# oec.net
KiCad netlist of a schematic drawn in EAGLE
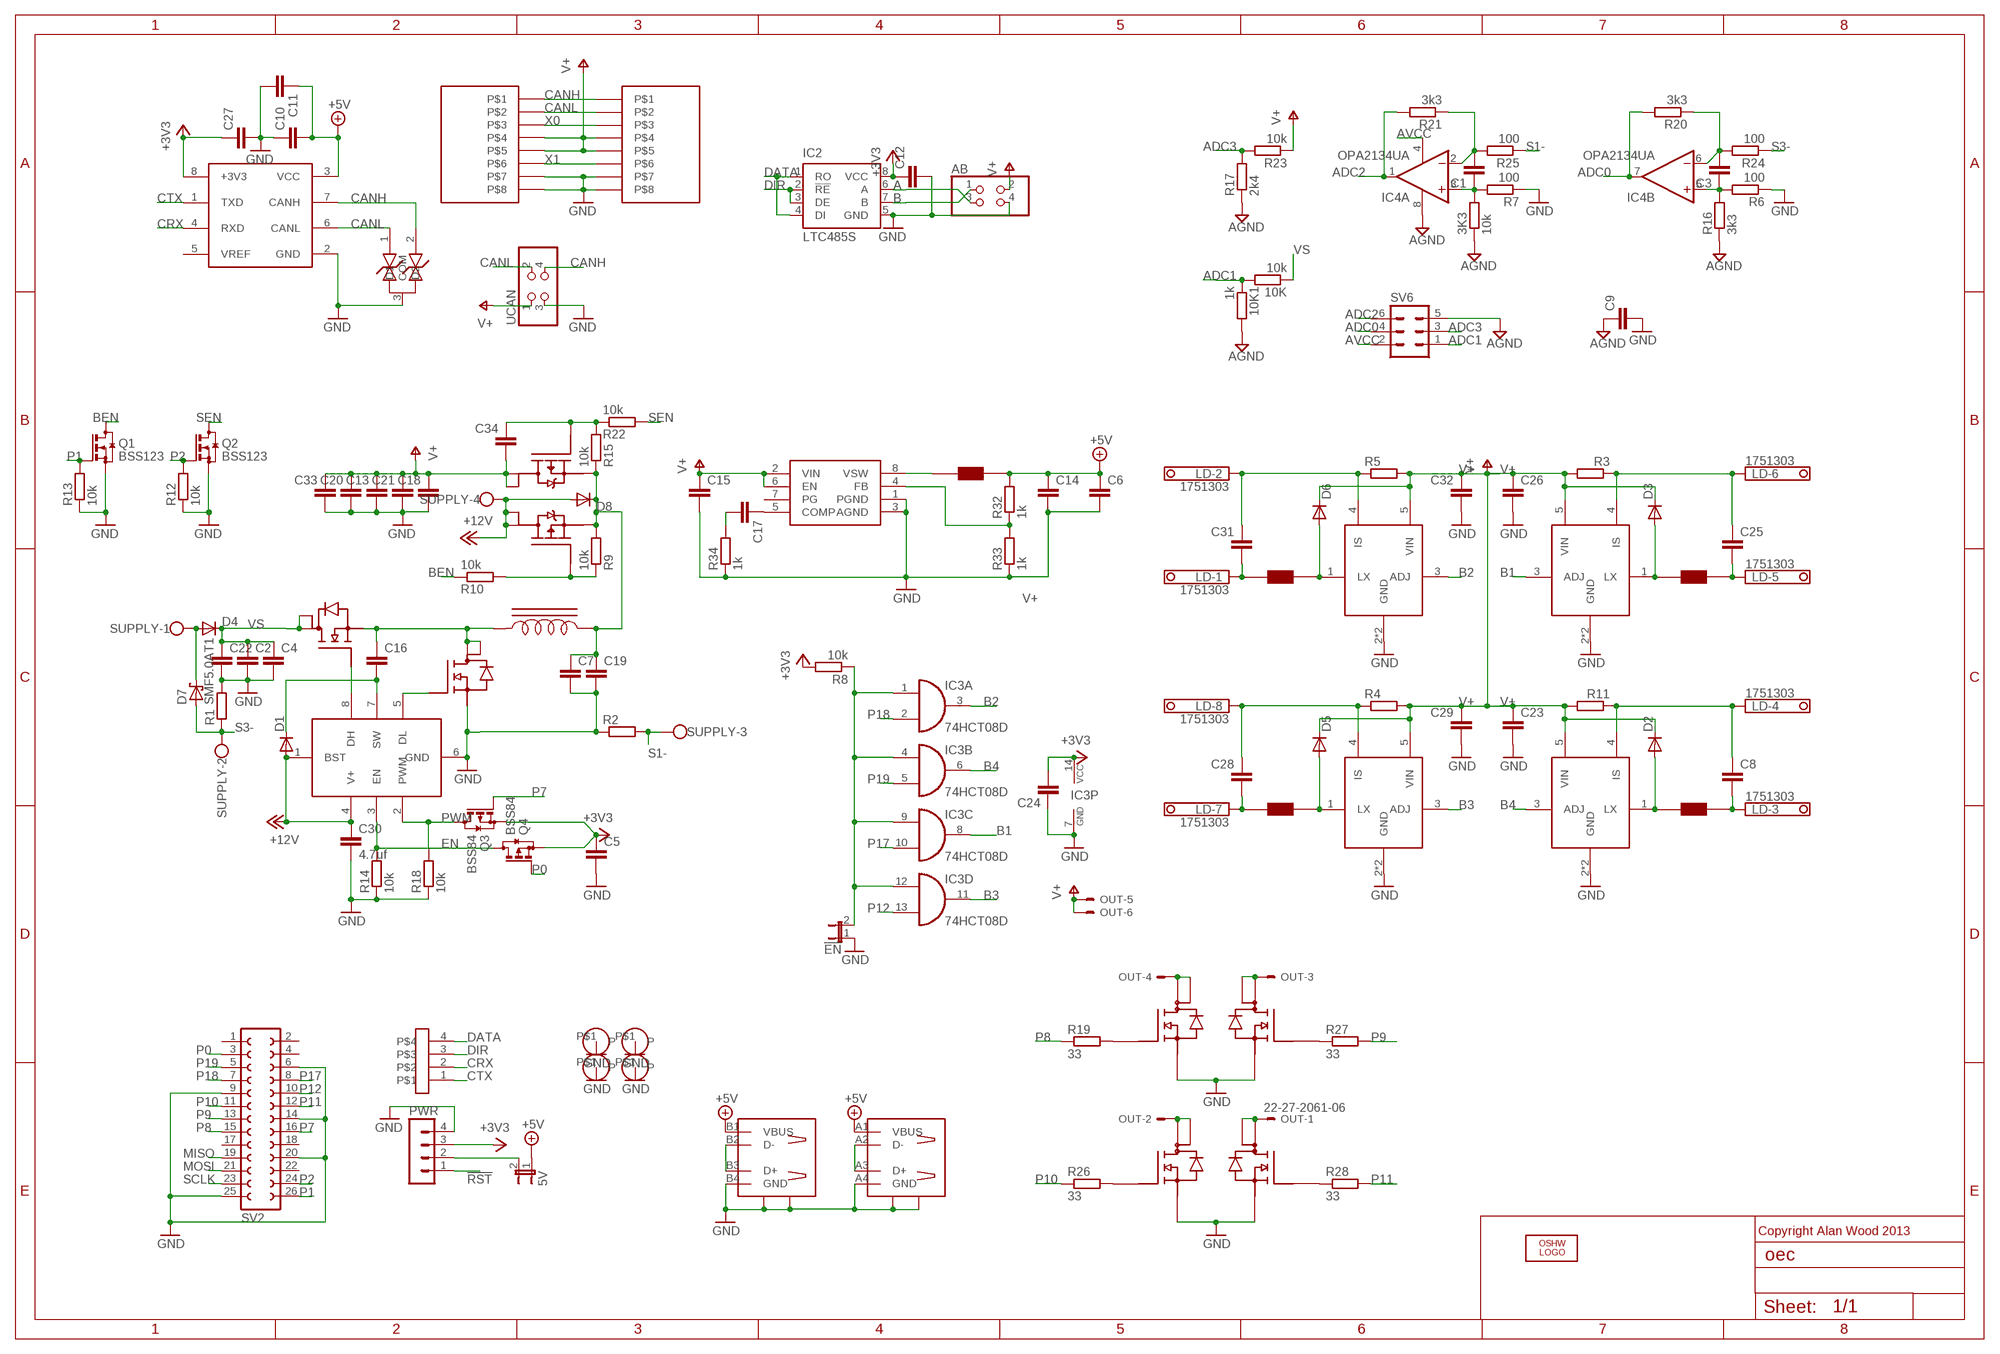
[diagram p0: schematic, sheet 1]

(export (version "E")
  (design (tool "Eeschema 10.0.6"))
  (components
    (comp (ref "!EN")
      (value "JP1E")
      (footprint "eagle-import:JP1")
      (libsource (lib "eagle-import") (part "JP1E"))
    )
    (comp (ref "3K3")
      (value "10k")
      (footprint "eagle-import:R0805")
      (libsource (lib "eagle-import") (part "R-EU_R0805"))
    )
    (comp (ref "5V")
      (value "JP1E")
      (footprint "eagle-import:JP1")
      (libsource (lib "eagle-import") (part "JP1E"))
    )
    (comp (ref "10K")
      (value "10k")
      (footprint "eagle-import:R0805")
      (libsource (lib "eagle-import") (part "R-EU_R0805"))
    )
    (comp (ref "10K1")
      (value "1k")
      (footprint "eagle-import:R0805")
      (libsource (lib "eagle-import") (part "R-EU_R0805"))
    )
    (comp (ref "AB")
      (value "PINHD-2X2/90")
      (footprint "eagle-import:2X02_90")
      (libsource (lib "eagle-import") (part "PINHD-2X2/90"))
    )
    (comp (ref "C1")
      (value "C-EUC0805")
      (footprint "eagle-import:C0805")
      (libsource (lib "eagle-import") (part "C-EUC0805"))
    )
    (comp (ref "C2")
      (value "C-EUC1210")
      (footprint "eagle-import:C1210")
      (libsource (lib "eagle-import") (part "C-EUC1210"))
    )
    (comp (ref "C3")
      (value "C-EUC0805")
      (footprint "eagle-import:C0805")
      (libsource (lib "eagle-import") (part "C-EUC0805"))
    )
    (comp (ref "C4")
      (value "C-EUC1210")
      (footprint "eagle-import:C1210")
      (libsource (lib "eagle-import") (part "C-EUC1210"))
    )
    (comp (ref "C5")
      (value "C-EUC0805")
      (footprint "eagle-import:C0805")
      (libsource (lib "eagle-import") (part "C-EUC0805"))
    )
    (comp (ref "C6")
      (value "C-EUC1210")
      (footprint "eagle-import:C1210")
      (libsource (lib "eagle-import") (part "C-EUC1210"))
    )
    (comp (ref "C7")
      (value "C-EUC1210")
      (footprint "eagle-import:C1210")
      (libsource (lib "eagle-import") (part "C-EUC1210"))
    )
    (comp (ref "C8")
      (value "C-EUC1210")
      (footprint "eagle-import:C1210")
      (libsource (lib "eagle-import") (part "C-EUC1210"))
    )
    (comp (ref "C9")
      (value "C-EUC0805")
      (footprint "eagle-import:C0805")
      (libsource (lib "eagle-import") (part "C-EUC0805"))
    )
    (comp (ref "C10")
      (value "C-EUC1210")
      (footprint "eagle-import:C1210")
      (libsource (lib "eagle-import") (part "C-EUC1210"))
    )
    (comp (ref "C11")
      (value "C-EUC1210")
      (footprint "eagle-import:C1210")
      (libsource (lib "eagle-import") (part "C-EUC1210"))
    )
    (comp (ref "C12")
      (value "C-EUC0805")
      (footprint "eagle-import:C0805")
      (libsource (lib "eagle-import") (part "C-EUC0805"))
    )
    (comp (ref "C13")
      (value "C-EUC1210")
      (footprint "eagle-import:C1210")
      (libsource (lib "eagle-import") (part "C-EUC1210"))
    )
    (comp (ref "C14")
      (value "C-EUC1210")
      (footprint "eagle-import:C1210")
      (libsource (lib "eagle-import") (part "C-EUC1210"))
    )
    (comp (ref "C15")
      (value "C-EUC0805")
      (footprint "eagle-import:C0805")
      (libsource (lib "eagle-import") (part "C-EUC0805"))
    )
    (comp (ref "C16")
      (value "C-EUC0805")
      (footprint "eagle-import:C0805")
      (libsource (lib "eagle-import") (part "C-EUC0805"))
    )
    (comp (ref "C17")
      (value "C-EUC0805")
      (footprint "eagle-import:C0805")
      (libsource (lib "eagle-import") (part "C-EUC0805"))
    )
    (comp (ref "C18")
      (value "C-EUC1210")
      (footprint "eagle-import:C1210")
      (libsource (lib "eagle-import") (part "C-EUC1210"))
    )
    (comp (ref "C19")
      (value "C-EUC1210")
      (footprint "eagle-import:C1210")
      (libsource (lib "eagle-import") (part "C-EUC1210"))
    )
    (comp (ref "C20")
      (value "C-EUC1210")
      (footprint "eagle-import:C1210")
      (libsource (lib "eagle-import") (part "C-EUC1210"))
    )
    (comp (ref "C21")
      (value "C-EUC1210")
      (footprint "eagle-import:C1210")
      (libsource (lib "eagle-import") (part "C-EUC1210"))
    )
    (comp (ref "C22")
      (value "C-EUC1210")
      (footprint "eagle-import:C1210")
      (libsource (lib "eagle-import") (part "C-EUC1210"))
    )
    (comp (ref "C23")
      (value "C-EUC1210")
      (footprint "eagle-import:C1210")
      (libsource (lib "eagle-import") (part "C-EUC1210"))
    )
    (comp (ref "C24")
      (value "C-EUC0805")
      (footprint "eagle-import:C0805")
      (libsource (lib "eagle-import") (part "C-EUC0805"))
    )
    (comp (ref "C25")
      (value "C-EUC1210")
      (footprint "eagle-import:C1210")
      (libsource (lib "eagle-import") (part "C-EUC1210"))
    )
    (comp (ref "C26")
      (value "C-EUC1210")
      (footprint "eagle-import:C1210")
      (libsource (lib "eagle-import") (part "C-EUC1210"))
    )
    (comp (ref "C27")
      (value "C-EUC0805")
      (footprint "eagle-import:C0805")
      (libsource (lib "eagle-import") (part "C-EUC0805"))
    )
    (comp (ref "C28")
      (value "C-EUC1210")
      (footprint "eagle-import:C1210")
      (libsource (lib "eagle-import") (part "C-EUC1210"))
    )
    (comp (ref "C29")
      (value "C-EUC1210")
      (footprint "eagle-import:C1210")
      (libsource (lib "eagle-import") (part "C-EUC1210"))
    )
    (comp (ref "C30")
      (value "4.7uf")
      (footprint "eagle-import:C0805")
      (libsource (lib "eagle-import") (part "C-EUC0805"))
    )
    (comp (ref "C31")
      (value "C-EUC1210")
      (footprint "eagle-import:C1210")
      (libsource (lib "eagle-import") (part "C-EUC1210"))
    )
    (comp (ref "C32")
      (value "C-EUC1210")
      (footprint "eagle-import:C1210")
      (libsource (lib "eagle-import") (part "C-EUC1210"))
    )
    (comp (ref "C33")
      (value "C-EUC1210")
      (footprint "eagle-import:C1210")
      (libsource (lib "eagle-import") (part "C-EUC1210"))
    )
    (comp (ref "C34")
      (value "C-EUC0805")
      (footprint "eagle-import:C0805")
      (libsource (lib "eagle-import") (part "C-EUC0805"))
    )
    (comp (ref "COM")
      (value "4X1X2.54-HEADER")
      (footprint "eagle-import:2.54_HEADER_4W")
      (libsource (lib "eagle-import") (part "4X1X2.54-HEADER"))
    )
    (comp (ref "D1")
      (value "DIODE-SOD123")
      (footprint "eagle-import:SOD123")
      (libsource (lib "eagle-import") (part "DIODE-SOD123"))
    )
    (comp (ref "D2")
      (value "DIODE-SOD123")
      (footprint "eagle-import:SOD123")
      (libsource (lib "eagle-import") (part "DIODE-SOD123"))
    )
    (comp (ref "D3")
      (value "DIODE-SOD123")
      (footprint "eagle-import:SOD123")
      (libsource (lib "eagle-import") (part "DIODE-SOD123"))
    )
    (comp (ref "D4")
      (value "DIODE-DO214AC")
      (footprint "eagle-import:DO214AC")
      (libsource (lib "eagle-import") (part "DIODE-DO214AC"))
    )
    (comp (ref "D5")
      (value "DIODE-SOD123")
      (footprint "eagle-import:SOD123")
      (libsource (lib "eagle-import") (part "DIODE-SOD123"))
    )
    (comp (ref "D6")
      (value "DIODE-SOD123")
      (footprint "eagle-import:SOD123")
      (libsource (lib "eagle-import") (part "DIODE-SOD123"))
    )
    (comp (ref "D7")
      (value "SMF5.0AT1")
      (footprint "eagle-import:SOD123FL")
      (libsource (lib "eagle-import") (part "SMF5.0AT1"))
    )
    (comp (ref "D8")
      (value "DIODE-DO214AC")
      (footprint "eagle-import:DO214AC")
      (libsource (lib "eagle-import") (part "DIODE-DO214AC"))
    )
    (comp (ref "IC2")
      (value "LTC485S")
      (footprint "eagle-import:SOIC8")
      (libsource (lib "eagle-import") (part "LTC485S"))
    )
    (comp (ref "IC3")
      (value "74HCT08D")
      (footprint "eagle-import:SO14")
      (libsource (lib "eagle-import") (part "7408DHCT"))
    )
    (comp (ref "IC4")
      (value "OPA2134UA")
      (footprint "eagle-import:SO08")
      (libsource (lib "eagle-import") (part "OPA2UA134"))
    )
    (comp (ref "LD")
      (value "1751303")
      (footprint "eagle-import:1751303")
      (libsource (lib "eagle-import") (part "1751303"))
    )
    (comp (ref "LOGO1")
      (value "OSHW_LOGO_FILLX0200-NT")
      (footprint "eagle-import:OSHW_FILLX200_NOTEXT")
      (libsource (lib "eagle-import") (part "OSHW_LOGO_FILLX0200-NT"))
    )
    (comp (ref "OUT")
      (value "22-27-2061-06")
      (footprint "eagle-import:6410-06")
      (libsource (lib "eagle-import") (part "22-?-0627-2061"))
    )
    (comp (ref "PWR")
      (value "MA04-1")
      (footprint "eagle-import:MA04-1")
      (libsource (lib "eagle-import") (part "MA04-1"))
    )
    (comp (ref "Q1")
      (value "BSS123")
      (footprint "eagle-import:SOT23")
      (libsource (lib "eagle-import") (part "BSS123"))
    )
    (comp (ref "Q2")
      (value "BSS123")
      (footprint "eagle-import:SOT23")
      (libsource (lib "eagle-import") (part "BSS123"))
    )
    (comp (ref "Q3")
      (value "BSS84")
      (footprint "eagle-import:SOT23")
      (libsource (lib "eagle-import") (part "BSS84"))
    )
    (comp (ref "Q4")
      (value "BSS84")
      (footprint "eagle-import:SOT23")
      (libsource (lib "eagle-import") (part "BSS84"))
    )
    (comp (ref "R1")
      (value "R-EU_R1206")
      (footprint "eagle-import:R1206")
      (libsource (lib "eagle-import") (part "resistor_R-EU_R1206"))
    )
    (comp (ref "R2")
      (value "R-EU_R1206")
      (footprint "eagle-import:R1206")
      (libsource (lib "eagle-import") (part "resistor_R-EU_R1206"))
    )
    (comp (ref "R3")
      (value "R-EU_R1210")
      (footprint "eagle-import:R1210")
      (libsource (lib "eagle-import") (part "resistor_R-EU_R1210"))
    )
    (comp (ref "R4")
      (value "R-EU_R1210")
      (footprint "eagle-import:R1210")
      (libsource (lib "eagle-import") (part "resistor_R-EU_R1210"))
    )
    (comp (ref "R5")
      (value "R-EU_R1210")
      (footprint "eagle-import:R1210")
      (libsource (lib "eagle-import") (part "resistor_R-EU_R1210"))
    )
    (comp (ref "R6")
      (value "100")
      (footprint "eagle-import:R0805")
      (libsource (lib "eagle-import") (part "R-EU_R0805"))
    )
    (comp (ref "R7")
      (value "100")
      (footprint "eagle-import:R0805")
      (libsource (lib "eagle-import") (part "R-EU_R0805"))
    )
    (comp (ref "R8")
      (value "10k")
      (footprint "eagle-import:R0805")
      (libsource (lib "eagle-import") (part "R-EU_R0805"))
    )
    (comp (ref "R9")
      (value "10k")
      (footprint "eagle-import:R0805")
      (libsource (lib "eagle-import") (part "R-EU_R0805"))
    )
    (comp (ref "R10")
      (value "10k")
      (footprint "eagle-import:R0805")
      (libsource (lib "eagle-import") (part "R-EU_R0805"))
    )
    (comp (ref "R11")
      (value "R-EU_R1210")
      (footprint "eagle-import:R1210")
      (libsource (lib "eagle-import") (part "resistor_R-EU_R1210"))
    )
    (comp (ref "R12")
      (value "10k")
      (footprint "eagle-import:R0805")
      (libsource (lib "eagle-import") (part "R-EU_R0805"))
    )
    (comp (ref "R13")
      (value "10k")
      (footprint "eagle-import:R0805")
      (libsource (lib "eagle-import") (part "R-EU_R0805"))
    )
    (comp (ref "R14")
      (value "10k")
      (footprint "eagle-import:R0805")
      (libsource (lib "eagle-import") (part "R-EU_R0805"))
    )
    (comp (ref "R15")
      (value "10k")
      (footprint "eagle-import:R0805")
      (libsource (lib "eagle-import") (part "R-EU_R0805"))
    )
    (comp (ref "R16")
      (value "3k3")
      (footprint "eagle-import:R0805")
      (libsource (lib "eagle-import") (part "R-EU_R0805"))
    )
    (comp (ref "R17")
      (value "2k4")
      (footprint "eagle-import:R0805")
      (libsource (lib "eagle-import") (part "R-EU_R0805"))
    )
    (comp (ref "R18")
      (value "10k")
      (footprint "eagle-import:R0805")
      (libsource (lib "eagle-import") (part "R-EU_R0805"))
    )
    (comp (ref "R19")
      (value "33")
      (footprint "eagle-import:R0603")
      (libsource (lib "eagle-import") (part "resistor_R-EU_R0603"))
    )
    (comp (ref "R20")
      (value "3k3")
      (footprint "eagle-import:R0805")
      (libsource (lib "eagle-import") (part "R-EU_R0805"))
    )
    (comp (ref "R21")
      (value "3k3")
      (footprint "eagle-import:R0805")
      (libsource (lib "eagle-import") (part "R-EU_R0805"))
    )
    (comp (ref "R22")
      (value "10k")
      (footprint "eagle-import:R0805")
      (libsource (lib "eagle-import") (part "R-EU_R0805"))
    )
    (comp (ref "R23")
      (value "10k")
      (footprint "eagle-import:R0805")
      (libsource (lib "eagle-import") (part "R-EU_R0805"))
    )
    (comp (ref "R24")
      (value "100")
      (footprint "eagle-import:R0805")
      (libsource (lib "eagle-import") (part "R-EU_R0805"))
    )
    (comp (ref "R25")
      (value "100")
      (footprint "eagle-import:R0805")
      (libsource (lib "eagle-import") (part "R-EU_R0805"))
    )
    (comp (ref "R26")
      (value "33")
      (footprint "eagle-import:R0603")
      (libsource (lib "eagle-import") (part "resistor_R-EU_R0603"))
    )
    (comp (ref "R27")
      (value "33")
      (footprint "eagle-import:R0603")
      (libsource (lib "eagle-import") (part "resistor_R-EU_R0603"))
    )
    (comp (ref "R28")
      (value "33")
      (footprint "eagle-import:R0603")
      (libsource (lib "eagle-import") (part "resistor_R-EU_R0603"))
    )
    (comp (ref "R32")
      (value "1k")
      (footprint "eagle-import:R0805")
      (libsource (lib "eagle-import") (part "R-EU_R0805"))
    )
    (comp (ref "R33")
      (value "1k")
      (footprint "eagle-import:R0805")
      (libsource (lib "eagle-import") (part "R-EU_R0805"))
    )
    (comp (ref "R34")
      (value "1k")
      (footprint "eagle-import:R0805")
      (libsource (lib "eagle-import") (part "R-EU_R0805"))
    )
    (comp (ref "SUPPLY")
      (value "W237-4")
      (footprint "eagle-import:W237-4")
      (libsource (lib "eagle-import") (part "W237-4"))
    )
    (comp (ref "SV2")
      (value "FE13-2")
      (footprint "eagle-import:FE13-2")
      (libsource (lib "eagle-import") (part "FE13-2"))
    )
    (comp (ref "SV6")
      (value "MA03-2")
      (footprint "eagle-import:MA03-2")
      (libsource (lib "eagle-import") (part "MA03-2"))
    )
    (comp (ref "U$1")
      (value "HOLE-2.5MM")
      (footprint "eagle-import:2.5MM-HOLE")
      (libsource (lib "eagle-import") (part "HOLE-2.5MM"))
    )
    (comp (ref "U$2")
      (value "HOLE-2.5MM")
      (footprint "eagle-import:2.5MM-HOLE")
      (libsource (lib "eagle-import") (part "HOLE-2.5MM"))
    )
    (comp (ref "U$3")
      (value "HOLE-2.5MM")
      (footprint "eagle-import:2.5MM-HOLE")
      (libsource (lib "eagle-import") (part "HOLE-2.5MM"))
    )
    (comp (ref "U$4")
      (value "HOLE-2.5MM")
      (footprint "eagle-import:2.5MM-HOLE")
      (libsource (lib "eagle-import") (part "HOLE-2.5MM"))
    )
    (comp (ref "U$5")
      (value "NCP3170SOIC-8")
      (footprint "eagle-import:SOIC-8-NARROW")
      (libsource (lib "eagle-import") (part "NCP3170SOIC-8"))
    )
    (comp (ref "U$6")
      (value "NTMD4820NR2G")
      (footprint "eagle-import:SOIC-8-NARROW")
      (libsource (lib "eagle-import") (part "NTMD4820NR2G"))
    )
    (comp (ref "U$7")
      (value "AMIS-3063")
      (footprint "eagle-import:SOIC-8-NARROW")
      (libsource (lib "eagle-import") (part "AMIS-3063"))
    )
    (comp (ref "U$8")
      (value "NTMD4820NR2G")
      (footprint "eagle-import:SOIC-8-NARROW")
      (libsource (lib "eagle-import") (part "NTMD4820NR2G"))
    )
    (comp (ref "U$9")
      (value "NRS6045T330MMGK")
      (footprint "eagle-import:TAIKO-YUDEN-6045")
      (libsource (lib "eagle-import") (part "NRS6045T330MMGK"))
    )
    (comp (ref "U$12")
      (value "NCP3420")
      (footprint "eagle-import:SO8")
      (libsource (lib "eagle-import") (part "NCP3420"))
    )
    (comp (ref "U$13")
      (value "RJHSE-5080")
      (footprint "eagle-import:RJ45")
      (libsource (lib "eagle-import") (part "RJHSE-5080"))
    )
    (comp (ref "U$14")
      (value "RJHSE-5080")
      (footprint "eagle-import:RJ45")
      (libsource (lib "eagle-import") (part "RJHSE-5080"))
    )
    (comp (ref "U$15")
      (value "DR127-XXX")
      (footprint "eagle-import:DR127")
      (libsource (lib "eagle-import") (part "DR127-XXX"))
    )
    (comp (ref "U$16")
      (value "DUAL-USBA-PTH-5787617-1")
      (footprint "eagle-import:DUAL-USBA-PTH")
      (libsource (lib "eagle-import") (part "DUAL-USBA-PTH-5787617-1"))
    )
    (comp (ref "U$17")
      (value "NUP2105L")
      (footprint "eagle-import:SOT23")
      (libsource (lib "eagle-import") (part "NUP2105L"))
    )
    (comp (ref "U$19")
      (value "SI49255DD")
      (footprint "eagle-import:SO8")
      (libsource (lib "eagle-import") (part "SI49255DD"))
    )
    (comp (ref "U$20")
      (value "IRF9358PBF")
      (footprint "eagle-import:SO8")
      (libsource (lib "eagle-import") (part "IRF9358PBF"))
    )
    (comp (ref "U$25")
      (value "ZLED7X20")
      (footprint "eagle-import:SOT89-5")
      (libsource (lib "eagle-import") (part "ZLED7X20"))
    )
    (comp (ref "U$27")
      (value "ZLED7X20")
      (footprint "eagle-import:SOT89-5")
      (libsource (lib "eagle-import") (part "ZLED7X20"))
    )
    (comp (ref "U$29")
      (value "ZLED7X20")
      (footprint "eagle-import:SOT89-5")
      (libsource (lib "eagle-import") (part "ZLED7X20"))
    )
    (comp (ref "U$31")
      (value "ZLED7X20")
      (footprint "eagle-import:SOT89-5")
      (libsource (lib "eagle-import") (part "ZLED7X20"))
    )
    (comp (ref "U$33")
      (value "NR5040T330M")
      (footprint "eagle-import:TAIKO-YUDEN-5040")
      (libsource (lib "eagle-import") (part "NR5040T330M"))
    )
    (comp (ref "U$34")
      (value "NR5040T330M")
      (footprint "eagle-import:TAIKO-YUDEN-5040")
      (libsource (lib "eagle-import") (part "NR5040T330M"))
    )
    (comp (ref "U$35")
      (value "NR5040T330M")
      (footprint "eagle-import:TAIKO-YUDEN-5040")
      (libsource (lib "eagle-import") (part "NR5040T330M"))
    )
    (comp (ref "U$36")
      (value "NR5040T330M")
      (footprint "eagle-import:TAIKO-YUDEN-5040")
      (libsource (lib "eagle-import") (part "NR5040T330M"))
    )
    (comp (ref "UCAN")
      (value "PINHD-2X2")
      (footprint "eagle-import:2X02")
      (libsource (lib "eagle-import") (part "PINHD-2X2"))
    )
  )
  (nets
    (net (code "1") (name "+3V3") (class "Default")
      (node (ref "C12") (pin "1") (pinfunction "1_1") (pintype "passive"))
      (node (ref "C24") (pin "2") (pinfunction "2_2") (pintype "passive"))
      (node (ref "C27") (pin "1") (pinfunction "1_1") (pintype "passive"))
      (node (ref "C5") (pin "1") (pinfunction "1_1") (pintype "passive"))
      (node (ref "IC2") (pin "8") (pinfunction "VCC_8") (pintype "input"))
      (node (ref "IC3") (pin "14") (pinfunction "VCC_14") (pintype "power_in"))
      (node (ref "PWR") (pin "3") (pinfunction "3_3") (pintype "passive"))
      (node (ref "Q3") (pin "2") (pinfunction "S_2") (pintype "passive"))
      (node (ref "Q4") (pin "2") (pinfunction "S_2") (pintype "passive"))
      (node (ref "R8") (pin "2") (pinfunction "2_2") (pintype "passive"))
      (node (ref "U$7") (pin "8") (pinfunction "+3V3_8") (pintype "power_in"))
    )
    (net (code "2") (name "+5V") (class "Default")
      (node (ref "5V") (pin "1") (pinfunction "1_1") (pintype "passive"))
      (node (ref "C10") (pin "2") (pinfunction "2_2") (pintype "passive"))
      (node (ref "C11") (pin "1") (pinfunction "1_1") (pintype "passive"))
      (node (ref "C14") (pin "1") (pinfunction "1_1") (pintype "passive"))
      (node (ref "C6") (pin "1") (pinfunction "1_1") (pintype "passive"))
      (node (ref "R32") (pin "2") (pinfunction "2_2") (pintype "passive"))
      (node (ref "U$16") (pin "A1") (pinfunction "VBUS_A1") (pintype "power_in"))
      (node (ref "U$16") (pin "B1") (pinfunction "VBUS_B1") (pintype "power_in"))
      (node (ref "U$7") (pin "3") (pinfunction "VCC_3") (pintype "power_in"))
      (node (ref "U$9") (pin "2") (pinfunction "P$2_2") (pintype "passive"))
    )
    (net (code "3") (name "+12V") (class "Default")
      (node (ref "C30") (pin "1") (pinfunction "1_1") (pintype "passive"))
      (node (ref "D1") (pin "A") (pinfunction "A_A") (pintype "passive"))
      (node (ref "D8") (pin "A") (pinfunction "A_A") (pintype "passive"))
      (node (ref "SUPPLY") (pin "4") (pinfunction "KL_4") (pintype "passive"))
      (node (ref "U$12") (pin "1") (pinfunction "BST_1") (pintype "passive"))
      (node (ref "U$12") (pin "4") (pinfunction "V+_4") (pintype "power_in"))
      (node (ref "U$19") (pin "7") (pinfunction "D_7") (pintype "passive"))
      (node (ref "U$19") (pin "8") (pinfunction "D_8") (pintype "passive"))
    )
    (net (code "4") (name "/A") (class "Default")
      (node (ref "AB") (pin "3") (pinfunction "3_3") (pintype "passive"))
      (node (ref "IC2") (pin "6") (pinfunction "A_6") (pintype "bidirectional"))
    )
    (net (code "5") (name "/ADC0") (class "Default")
      (node (ref "IC4") (pin "7") (pinfunction "OUT_7") (pintype "output"))
      (node (ref "R20") (pin "2") (pinfunction "2_2") (pintype "passive"))
      (node (ref "SV6") (pin "4") (pinfunction "4_4") (pintype "passive"))
    )
    (net (code "6") (name "/ADC1") (class "Default")
      (node (ref "10K") (pin "2") (pinfunction "2_2") (pintype "passive"))
      (node (ref "10K1") (pin "1") (pinfunction "1_1") (pintype "passive"))
      (node (ref "SV6") (pin "1") (pinfunction "1_1") (pintype "passive"))
    )
    (net (code "7") (name "/ADC2") (class "Default")
      (node (ref "IC4") (pin "1") (pinfunction "OUT_1") (pintype "output"))
      (node (ref "R21") (pin "2") (pinfunction "2_2") (pintype "passive"))
      (node (ref "SV6") (pin "6") (pinfunction "6_6") (pintype "passive"))
    )
    (net (code "8") (name "/ADC3") (class "Default")
      (node (ref "R17") (pin "2") (pinfunction "2_2") (pintype "passive"))
      (node (ref "R23") (pin "2") (pinfunction "2_2") (pintype "passive"))
      (node (ref "SV6") (pin "3") (pinfunction "3_3") (pintype "passive"))
    )
    (net (code "9") (name "/AVCC") (class "Default")
      (node (ref "IC4") (pin "4") (pinfunction "V-_4") (pintype "power_in"))
      (node (ref "SV6") (pin "2") (pinfunction "2_2") (pintype "passive"))
    )
    (net (code "10") (name "/B") (class "Default")
      (node (ref "AB") (pin "1") (pinfunction "1_1") (pintype "passive"))
      (node (ref "IC2") (pin "7") (pinfunction "B_7") (pintype "bidirectional"))
    )
    (net (code "11") (name "/B1") (class "Default")
      (node (ref "IC3") (pin "8") (pinfunction "O_8") (pintype "output"))
      (node (ref "U$27") (pin "3") (pinfunction "ADJ_3") (pintype "input"))
    )
    (net (code "12") (name "/B2") (class "Default")
      (node (ref "IC3") (pin "3") (pinfunction "O_3") (pintype "output"))
      (node (ref "U$31") (pin "3") (pinfunction "ADJ_3") (pintype "input"))
    )
    (net (code "13") (name "/B3") (class "Default")
      (node (ref "IC3") (pin "11") (pinfunction "O_11") (pintype "output"))
      (node (ref "U$29") (pin "3") (pinfunction "ADJ_3") (pintype "input"))
    )
    (net (code "14") (name "/B4") (class "Default")
      (node (ref "IC3") (pin "6") (pinfunction "O_6") (pintype "output"))
      (node (ref "U$25") (pin "3") (pinfunction "ADJ_3") (pintype "input"))
    )
    (net (code "15") (name "/BEN") (class "Default")
      (node (ref "Q1") (pin "3") (pinfunction "D_3") (pintype "passive"))
      (node (ref "R10") (pin "1") (pinfunction "1_1") (pintype "passive"))
    )
    (net (code "16") (name "/CANH") (class "Default")
      (node (ref "U$13") (pin "P$1") (pinfunction "P$1_P$1") (pintype "bidirectional"))
      (node (ref "U$14") (pin "P$1") (pinfunction "P$1_P$1") (pintype "bidirectional"))
      (node (ref "U$17") (pin "2") (pinfunction "D2_2") (pintype "passive"))
      (node (ref "U$7") (pin "7") (pinfunction "CANH_7") (pintype "bidirectional"))
      (node (ref "UCAN") (pin "4") (pinfunction "4_4") (pintype "passive"))
    )
    (net (code "17") (name "/CANL") (class "Default")
      (node (ref "U$13") (pin "P$2") (pinfunction "P$2_P$2") (pintype "bidirectional"))
      (node (ref "U$14") (pin "P$2") (pinfunction "P$2_P$2") (pintype "bidirectional"))
      (node (ref "U$17") (pin "1") (pinfunction "D1_1") (pintype "passive"))
      (node (ref "U$7") (pin "6") (pinfunction "CANL_6") (pintype "bidirectional"))
      (node (ref "UCAN") (pin "2") (pinfunction "2_2") (pintype "passive"))
    )
    (net (code "18") (name "/CRX") (class "Default")
      (node (ref "COM") (pin "2") (pinfunction "P$2_2") (pintype "bidirectional"))
      (node (ref "U$7") (pin "4") (pinfunction "RXD_4") (pintype "output"))
    )
    (net (code "19") (name "/CTX") (class "Default")
      (node (ref "COM") (pin "1") (pinfunction "P$1_1") (pintype "bidirectional"))
      (node (ref "U$7") (pin "1") (pinfunction "TXD_1") (pintype "input"))
    )
    (net (code "20") (name "/DATA") (class "Default")
      (node (ref "COM") (pin "4") (pinfunction "P$4_4") (pintype "bidirectional"))
      (node (ref "IC2") (pin "1") (pinfunction "RO_1") (pintype "output"))
      (node (ref "IC2") (pin "4") (pinfunction "DI_4") (pintype "input"))
    )
    (net (code "21") (name "/DIR") (class "Default")
      (node (ref "COM") (pin "3") (pinfunction "P$3_3") (pintype "bidirectional"))
      (node (ref "IC2") (pin "2") (pinfunction "~{RE}_2") (pintype "input"))
      (node (ref "IC2") (pin "3") (pinfunction "DE_3") (pintype "input"))
    )
    (net (code "22") (name "/EN") (class "Default")
      (node (ref "Q4") (pin "3") (pinfunction "D_3") (pintype "passive"))
      (node (ref "R14") (pin "2") (pinfunction "2_2") (pintype "passive"))
      (node (ref "U$12") (pin "3") (pinfunction "EN_3") (pintype "input"))
    )
    (net (code "23") (name "/MISO") (class "Default")
      (node (ref "SV2") (pin "19") (pinfunction "19_19") (pintype "passive"))
    )
    (net (code "24") (name "/MOSI") (class "Default")
      (node (ref "SV2") (pin "21") (pinfunction "21_21") (pintype "passive"))
    )
    (net (code "25") (name "/P0") (class "Default")
      (node (ref "Q4") (pin "1") (pinfunction "G_1") (pintype "passive"))
      (node (ref "SV2") (pin "3") (pinfunction "3_3") (pintype "passive"))
    )
    (net (code "26") (name "/P1") (class "Default")
      (node (ref "Q1") (pin "1") (pinfunction "G_1") (pintype "passive"))
      (node (ref "R13") (pin "2") (pinfunction "2_2") (pintype "passive"))
      (node (ref "SV2") (pin "26") (pinfunction "26_26") (pintype "passive"))
    )
    (net (code "27") (name "/P2") (class "Default")
      (node (ref "Q2") (pin "1") (pinfunction "G_1") (pintype "passive"))
      (node (ref "R12") (pin "2") (pinfunction "2_2") (pintype "passive"))
      (node (ref "SV2") (pin "24") (pinfunction "24_24") (pintype "passive"))
    )
    (net (code "28") (name "/P7") (class "Default")
      (node (ref "Q3") (pin "1") (pinfunction "G_1") (pintype "passive"))
      (node (ref "SV2") (pin "16") (pinfunction "16_16") (pintype "passive"))
    )
    (net (code "29") (name "/P8") (class "Default")
      (node (ref "R19") (pin "1") (pinfunction "1_1") (pintype "passive"))
      (node (ref "SV2") (pin "15") (pinfunction "15_15") (pintype "passive"))
    )
    (net (code "30") (name "/P9") (class "Default")
      (node (ref "R27") (pin "2") (pinfunction "2_2") (pintype "passive"))
      (node (ref "SV2") (pin "13") (pinfunction "13_13") (pintype "passive"))
    )
    (net (code "31") (name "/P10") (class "Default")
      (node (ref "R26") (pin "1") (pinfunction "1_1") (pintype "passive"))
      (node (ref "SV2") (pin "11") (pinfunction "11_11") (pintype "passive"))
    )
    (net (code "32") (name "/P11") (class "Default")
      (node (ref "R28") (pin "2") (pinfunction "2_2") (pintype "passive"))
      (node (ref "SV2") (pin "12") (pinfunction "12_12") (pintype "passive"))
    )
    (net (code "33") (name "/P12") (class "Default")
      (node (ref "IC3") (pin "13") (pinfunction "I1_13") (pintype "input"))
      (node (ref "SV2") (pin "10") (pinfunction "10_10") (pintype "passive"))
    )
    (net (code "34") (name "/P17") (class "Default")
      (node (ref "IC3") (pin "10") (pinfunction "I1_10") (pintype "input"))
      (node (ref "SV2") (pin "8") (pinfunction "8_8") (pintype "passive"))
    )
    (net (code "35") (name "/P18") (class "Default")
      (node (ref "IC3") (pin "2") (pinfunction "I1_2") (pintype "input"))
      (node (ref "SV2") (pin "7") (pinfunction "7_7") (pintype "passive"))
    )
    (net (code "36") (name "/P19") (class "Default")
      (node (ref "IC3") (pin "5") (pinfunction "I1_5") (pintype "input"))
      (node (ref "SV2") (pin "5") (pinfunction "5_5") (pintype "passive"))
    )
    (net (code "37") (name "/PWM") (class "Default")
      (node (ref "Q3") (pin "3") (pinfunction "D_3") (pintype "passive"))
      (node (ref "R18") (pin "2") (pinfunction "2_2") (pintype "passive"))
      (node (ref "U$12") (pin "2") (pinfunction "PWM_2") (pintype "input"))
    )
    (net (code "38") (name "/S1-") (class "Default")
      (node (ref "R2") (pin "2") (pinfunction "2_2") (pintype "passive"))
      (node (ref "R25") (pin "1") (pinfunction "1_1") (pintype "passive"))
      (node (ref "SUPPLY") (pin "3") (pinfunction "KL_3") (pintype "passive"))
    )
    (net (code "39") (name "/S3-") (class "Default")
      (node (ref "D7") (pin "A") (pinfunction "A_A") (pintype "passive"))
      (node (ref "R1") (pin "1") (pinfunction "1_1") (pintype "passive"))
      (node (ref "R24") (pin "1") (pinfunction "1_1") (pintype "passive"))
      (node (ref "SUPPLY") (pin "2") (pinfunction "KL_2") (pintype "passive"))
    )
    (net (code "40") (name "/SCLK") (class "Default")
      (node (ref "SV2") (pin "23") (pinfunction "23_23") (pintype "passive"))
    )
    (net (code "41") (name "/SEN") (class "Default")
      (node (ref "Q2") (pin "3") (pinfunction "D_3") (pintype "passive"))
      (node (ref "R22") (pin "2") (pinfunction "2_2") (pintype "passive"))
    )
    (net (code "42") (name "/VS") (class "Default")
      (node (ref "10K") (pin "1") (pinfunction "1_1") (pintype "passive"))
      (node (ref "C2") (pin "1") (pinfunction "1_1") (pintype "passive"))
      (node (ref "C22") (pin "1") (pinfunction "1_1") (pintype "passive"))
      (node (ref "C4") (pin "1") (pinfunction "1_1") (pintype "passive"))
      (node (ref "D4") (pin "C") (pinfunction "C_C") (pintype "passive"))
      (node (ref "U$20") (pin "7") (pinfunction "D_7") (pintype "passive"))
      (node (ref "U$20") (pin "8") (pinfunction "D_8") (pintype "passive"))
    )
    (net (code "43") (name "/X0") (class "Default")
      (node (ref "U$13") (pin "P$3") (pinfunction "P$3_P$3") (pintype "bidirectional"))
      (node (ref "U$14") (pin "P$3") (pinfunction "P$3_P$3") (pintype "bidirectional"))
    )
    (net (code "44") (name "/X1") (class "Default")
      (node (ref "U$13") (pin "P$6") (pinfunction "P$6_P$6") (pintype "bidirectional"))
      (node (ref "U$14") (pin "P$6") (pinfunction "P$6_P$6") (pintype "bidirectional"))
    )
    (net (code "45") (name "/~{RST}") (class "Default")
      (node (ref "PWR") (pin "1") (pinfunction "1_1") (pintype "passive"))
    )
    (net (code "46") (name "AGND") (class "Default")
      (node (ref "10K1") (pin "2") (pinfunction "2_2") (pintype "passive"))
      (node (ref "3K3") (pin "1") (pinfunction "1_1") (pintype "passive"))
      (node (ref "C9") (pin "1") (pinfunction "1_1") (pintype "passive"))
      (node (ref "IC4") (pin "8") (pinfunction "V+_8") (pintype "power_in"))
      (node (ref "R16") (pin "1") (pinfunction "1_1") (pintype "passive"))
      (node (ref "R17") (pin "1") (pinfunction "1_1") (pintype "passive"))
      (node (ref "SV6") (pin "5") (pinfunction "5_5") (pintype "passive"))
    )
    (net (code "47") (name "GND") (class "Default")
      (node (ref "!EN") (pin "1") (pinfunction "1_1") (pintype "passive"))
      (node (ref "AB") (pin "4") (pinfunction "4_4") (pintype "passive"))
      (node (ref "C10") (pin "1") (pinfunction "1_1") (pintype "passive"))
      (node (ref "C11") (pin "2") (pinfunction "2_2") (pintype "passive"))
      (node (ref "C12") (pin "2") (pinfunction "2_2") (pintype "passive"))
      (node (ref "C13") (pin "2") (pinfunction "2_2") (pintype "passive"))
      (node (ref "C14") (pin "2") (pinfunction "2_2") (pintype "passive"))
      (node (ref "C15") (pin "2") (pinfunction "2_2") (pintype "passive"))
      (node (ref "C18") (pin "2") (pinfunction "2_2") (pintype "passive"))
      (node (ref "C19") (pin "2") (pinfunction "2_2") (pintype "passive"))
      (node (ref "C2") (pin "2") (pinfunction "2_2") (pintype "passive"))
      (node (ref "C20") (pin "2") (pinfunction "2_2") (pintype "passive"))
      (node (ref "C21") (pin "2") (pinfunction "2_2") (pintype "passive"))
      (node (ref "C22") (pin "2") (pinfunction "2_2") (pintype "passive"))
      (node (ref "C23") (pin "2") (pinfunction "2_2") (pintype "passive"))
      (node (ref "C24") (pin "1") (pinfunction "1_1") (pintype "passive"))
      (node (ref "C26") (pin "2") (pinfunction "2_2") (pintype "passive"))
      (node (ref "C27") (pin "2") (pinfunction "2_2") (pintype "passive"))
      (node (ref "C29") (pin "2") (pinfunction "2_2") (pintype "passive"))
      (node (ref "C30") (pin "2") (pinfunction "2_2") (pintype "passive"))
      (node (ref "C32") (pin "2") (pinfunction "2_2") (pintype "passive"))
      (node (ref "C33") (pin "2") (pinfunction "2_2") (pintype "passive"))
      (node (ref "C4") (pin "2") (pinfunction "2_2") (pintype "passive"))
      (node (ref "C5") (pin "2") (pinfunction "2_2") (pintype "passive"))
      (node (ref "C6") (pin "2") (pinfunction "2_2") (pintype "passive"))
      (node (ref "C7") (pin "2") (pinfunction "2_2") (pintype "passive"))
      (node (ref "C9") (pin "2") (pinfunction "2_2") (pintype "passive"))
      (node (ref "IC2") (pin "5") (pinfunction "GND_5") (pintype "input"))
      (node (ref "IC3") (pin "7") (pinfunction "GND_7") (pintype "power_in"))
      (node (ref "PWR") (pin "4") (pinfunction "4_4") (pintype "passive"))
      (node (ref "Q1") (pin "2") (pinfunction "S_2") (pintype "passive"))
      (node (ref "Q2") (pin "2") (pinfunction "S_2") (pintype "passive"))
      (node (ref "R1") (pin "2") (pinfunction "2_2") (pintype "passive"))
      (node (ref "R12") (pin "1") (pinfunction "1_1") (pintype "passive"))
      (node (ref "R13") (pin "1") (pinfunction "1_1") (pintype "passive"))
      (node (ref "R14") (pin "1") (pinfunction "1_1") (pintype "passive"))
      (node (ref "R18") (pin "1") (pinfunction "1_1") (pintype "passive"))
      (node (ref "R2") (pin "1") (pinfunction "1_1") (pintype "passive"))
      (node (ref "R33") (pin "1") (pinfunction "1_1") (pintype "passive"))
      (node (ref "R34") (pin "1") (pinfunction "1_1") (pintype "passive"))
      (node (ref "R6") (pin "1") (pinfunction "1_1") (pintype "passive"))
      (node (ref "R7") (pin "1") (pinfunction "1_1") (pintype "passive"))
      (node (ref "SV2") (pin "14") (pinfunction "14_14") (pintype "passive"))
      (node (ref "SV2") (pin "20") (pinfunction "20_20") (pintype "passive"))
      (node (ref "SV2") (pin "25") (pinfunction "25_25") (pintype "passive"))
      (node (ref "SV2") (pin "6") (pinfunction "6_6") (pintype "passive"))
      (node (ref "SV2") (pin "9") (pinfunction "9_9") (pintype "passive"))
      (node (ref "U$1") (pin "P$1") (pinfunction "P_P$1") (pintype "bidirectional"))
      (node (ref "U$12") (pin "6") (pinfunction "GND_6") (pintype "power_in"))
      (node (ref "U$13") (pin "P$7") (pinfunction "P$7_P$7") (pintype "bidirectional"))
      (node (ref "U$13") (pin "P$8") (pinfunction "P$8_P$8") (pintype "bidirectional"))
      (node (ref "U$14") (pin "P$7") (pinfunction "P$7_P$7") (pintype "bidirectional"))
      (node (ref "U$14") (pin "P$8") (pinfunction "P$8_P$8") (pintype "bidirectional"))
      (node (ref "U$16") (pin "A4") (pinfunction "GND_A4") (pintype "power_in"))
      (node (ref "U$16") (pin "B4") (pinfunction "GND_B4") (pintype "power_in"))
      (node (ref "U$16") (pin "SH2B") (pinfunction "SH_SH2B") (pintype "passive"))
      (node (ref "U$16") (pin "SH@1A") (pinfunction "SH_SH@1A") (pintype "passive"))
      (node (ref "U$16") (pin "SH@1B") (pinfunction "SH_SH@1B") (pintype "passive"))
      (node (ref "U$16") (pin "SH@2A") (pinfunction "SH_SH@2A") (pintype "passive"))
      (node (ref "U$17") (pin "3") (pinfunction "COM_3") (pintype "passive"))
      (node (ref "U$2") (pin "P$1") (pinfunction "P_P$1") (pintype "bidirectional"))
      (node (ref "U$20") (pin "3") (pinfunction "S_3") (pintype "passive"))
      (node (ref "U$25") (pin "2") (pinfunction "GND_2") (pintype "power_in"))
      (node (ref "U$25") (pin "2@1") (pinfunction "GND_2@1") (pintype "power_in"))
      (node (ref "U$27") (pin "2") (pinfunction "GND_2") (pintype "power_in"))
      (node (ref "U$27") (pin "2@1") (pinfunction "GND_2@1") (pintype "power_in"))
      (node (ref "U$29") (pin "2") (pinfunction "GND_2") (pintype "power_in"))
      (node (ref "U$29") (pin "2@1") (pinfunction "GND_2@1") (pintype "power_in"))
      (node (ref "U$3") (pin "P$1") (pinfunction "P_P$1") (pintype "bidirectional"))
      (node (ref "U$31") (pin "2") (pinfunction "GND_2") (pintype "power_in"))
      (node (ref "U$31") (pin "2@1") (pinfunction "GND_2@1") (pintype "power_in"))
      (node (ref "U$4") (pin "P$1") (pinfunction "P_P$1") (pintype "bidirectional"))
      (node (ref "U$5") (pin "1") (pinfunction "PGND_1") (pintype "power_in"))
      (node (ref "U$5") (pin "3") (pinfunction "AGND_3") (pintype "power_in"))
      (node (ref "U$6") (pin "1") (pinfunction "S1_1") (pintype "passive"))
      (node (ref "U$6") (pin "3") (pinfunction "S2_3") (pintype "passive"))
      (node (ref "U$7") (pin "2") (pinfunction "GND_2") (pintype "power_in"))
      (node (ref "U$8") (pin "1") (pinfunction "S1_1") (pintype "passive"))
      (node (ref "U$8") (pin "3") (pinfunction "S2_3") (pintype "passive"))
      (node (ref "UCAN") (pin "3") (pinfunction "3_3") (pintype "passive"))
    )
    (net (code "48") (name "Net-(5V-Pad2)") (class "Default")
      (node (ref "5V") (pin "2") (pinfunction "2_2") (pintype "passive"))
      (node (ref "PWR") (pin "2") (pinfunction "2_2") (pintype "passive"))
    )
    (net (code "49") (name "Net-(C17-Pad2)") (class "Default")
      (node (ref "C17") (pin "2") (pinfunction "2_2") (pintype "passive"))
      (node (ref "R34") (pin "2") (pinfunction "2_2") (pintype "passive"))
    )
    (net (code "50") (name "Net-(IC3A-I0)") (class "Default")
      (node (ref "!EN") (pin "2") (pinfunction "2_2") (pintype "passive"))
      (node (ref "IC3") (pin "1") (pinfunction "I0_1") (pintype "input"))
      (node (ref "IC3") (pin "12") (pinfunction "I0_12") (pintype "input"))
      (node (ref "IC3") (pin "4") (pinfunction "I0_4") (pintype "input"))
      (node (ref "IC3") (pin "9") (pinfunction "I0_9") (pintype "input"))
      (node (ref "R8") (pin "1") (pinfunction "1_1") (pintype "passive"))
    )
    (net (code "51") (name "Net-(IC4A-+IN)") (class "Default")
      (node (ref "3K3") (pin "2") (pinfunction "2_2") (pintype "passive"))
      (node (ref "C1") (pin "1") (pinfunction "1_1") (pintype "passive"))
      (node (ref "IC4") (pin "3") (pinfunction "+IN_3") (pintype "input"))
      (node (ref "R7") (pin "2") (pinfunction "2_2") (pintype "passive"))
    )
    (net (code "52") (name "Net-(IC4A--IN)") (class "Default")
      (node (ref "C1") (pin "2") (pinfunction "2_2") (pintype "passive"))
      (node (ref "IC4") (pin "2") (pinfunction "-IN_2") (pintype "input"))
      (node (ref "R21") (pin "1") (pinfunction "1_1") (pintype "passive"))
      (node (ref "R25") (pin "2") (pinfunction "2_2") (pintype "passive"))
    )
    (net (code "53") (name "Net-(IC4B-+IN)") (class "Default")
      (node (ref "C3") (pin "1") (pinfunction "1_1") (pintype "passive"))
      (node (ref "IC4") (pin "5") (pinfunction "+IN_5") (pintype "input"))
      (node (ref "R16") (pin "2") (pinfunction "2_2") (pintype "passive"))
      (node (ref "R6") (pin "2") (pinfunction "2_2") (pintype "passive"))
    )
    (net (code "54") (name "Net-(IC4B--IN)") (class "Default")
      (node (ref "C3") (pin "2") (pinfunction "2_2") (pintype "passive"))
      (node (ref "IC4") (pin "6") (pinfunction "-IN_6") (pintype "input"))
      (node (ref "R20") (pin "1") (pinfunction "1_1") (pintype "passive"))
      (node (ref "R24") (pin "2") (pinfunction "2_2") (pintype "passive"))
    )
    (net (code "55") (name "Net-(LDA-K)") (class "Default")
      (node (ref "C31") (pin "2") (pinfunction "2_2") (pintype "passive"))
      (node (ref "LD") (pin "1") (pinfunction "K_1") (pintype "passive"))
      (node (ref "U$33") (pin "1") (pinfunction "P$1_1") (pintype "passive"))
    )
    (net (code "56") (name "Net-(LDB-K)") (class "Default")
      (node (ref "C31") (pin "1") (pinfunction "1_1") (pintype "passive"))
      (node (ref "LD") (pin "2") (pinfunction "K_2") (pintype "passive"))
      (node (ref "R5") (pin "1") (pinfunction "1_1") (pintype "passive"))
      (node (ref "U$31") (pin "4") (pinfunction "IS_4") (pintype "passive"))
    )
    (net (code "57") (name "Net-(LDC-K)") (class "Default")
      (node (ref "C8") (pin "2") (pinfunction "2_2") (pintype "passive"))
      (node (ref "LD") (pin "3") (pinfunction "K_3") (pintype "passive"))
      (node (ref "U$36") (pin "2") (pinfunction "P$2_2") (pintype "passive"))
    )
    (net (code "58") (name "Net-(LDD-K)") (class "Default")
      (node (ref "C8") (pin "1") (pinfunction "1_1") (pintype "passive"))
      (node (ref "LD") (pin "4") (pinfunction "K_4") (pintype "passive"))
      (node (ref "R11") (pin "1") (pinfunction "1_1") (pintype "passive"))
      (node (ref "U$25") (pin "4") (pinfunction "IS_4") (pintype "passive"))
    )
    (net (code "59") (name "Net-(LDE-K)") (class "Default")
      (node (ref "C25") (pin "2") (pinfunction "2_2") (pintype "passive"))
      (node (ref "LD") (pin "5") (pinfunction "K_5") (pintype "passive"))
      (node (ref "U$34") (pin "2") (pinfunction "P$2_2") (pintype "passive"))
    )
    (net (code "60") (name "Net-(LDF-K)") (class "Default")
      (node (ref "C25") (pin "1") (pinfunction "1_1") (pintype "passive"))
      (node (ref "LD") (pin "6") (pinfunction "K_6") (pintype "passive"))
      (node (ref "R3") (pin "1") (pinfunction "1_1") (pintype "passive"))
      (node (ref "U$27") (pin "4") (pinfunction "IS_4") (pintype "passive"))
    )
    (net (code "61") (name "Net-(LDG-K)") (class "Default")
      (node (ref "C28") (pin "2") (pinfunction "2_2") (pintype "passive"))
      (node (ref "LD") (pin "7") (pinfunction "K_7") (pintype "passive"))
      (node (ref "U$35") (pin "1") (pinfunction "P$1_1") (pintype "passive"))
    )
    (net (code "62") (name "Net-(LDH-K)") (class "Default")
      (node (ref "C28") (pin "1") (pinfunction "1_1") (pintype "passive"))
      (node (ref "LD") (pin "8") (pinfunction "K_8") (pintype "passive"))
      (node (ref "R4") (pin "1") (pinfunction "1_1") (pintype "passive"))
      (node (ref "U$29") (pin "4") (pinfunction "IS_4") (pintype "passive"))
    )
    (net (code "63") (name "Net-(OUTA-S)") (class "Default")
      (node (ref "OUT") (pin "1") (pinfunction "S_1") (pintype "passive"))
      (node (ref "U$8") (pin "5") (pinfunction "DP2_5") (pintype "passive"))
      (node (ref "U$8") (pin "6") (pinfunction "D2_6") (pintype "passive"))
    )
    (net (code "64") (name "Net-(OUTB-S)") (class "Default")
      (node (ref "OUT") (pin "2") (pinfunction "S_2") (pintype "passive"))
      (node (ref "U$8") (pin "7") (pinfunction "DP1_7") (pintype "passive"))
      (node (ref "U$8") (pin "8") (pinfunction "D1_8") (pintype "passive"))
    )
    (net (code "65") (name "Net-(OUTC-S)") (class "Default")
      (node (ref "OUT") (pin "3") (pinfunction "S_3") (pintype "passive"))
      (node (ref "U$6") (pin "5") (pinfunction "DP2_5") (pintype "passive"))
      (node (ref "U$6") (pin "6") (pinfunction "D2_6") (pintype "passive"))
    )
    (net (code "66") (name "Net-(OUTD-S)") (class "Default")
      (node (ref "OUT") (pin "4") (pinfunction "S_4") (pintype "passive"))
      (node (ref "U$6") (pin "7") (pinfunction "DP1_7") (pintype "passive"))
      (node (ref "U$6") (pin "8") (pinfunction "D1_8") (pintype "passive"))
    )
    (net (code "67") (name "Net-(SUPPLYA-KL)") (class "Default")
      (node (ref "D4") (pin "A") (pinfunction "A_A") (pintype "passive"))
      (node (ref "D7") (pin "C") (pinfunction "C_C") (pintype "passive"))
      (node (ref "SUPPLY") (pin "1") (pinfunction "KL_1") (pintype "passive"))
    )
    (net (code "68") (name "Net-(U$5-COMP)") (class "Default")
      (node (ref "C17") (pin "1") (pinfunction "1_1") (pintype "passive"))
      (node (ref "U$5") (pin "5") (pinfunction "COMP_5") (pintype "passive"))
    )
    (net (code "69") (name "Net-(U$5-FB)") (class "Default")
      (node (ref "R32") (pin "1") (pinfunction "1_1") (pintype "passive"))
      (node (ref "R33") (pin "2") (pinfunction "2_2") (pintype "passive"))
      (node (ref "U$5") (pin "4") (pinfunction "FB_4") (pintype "input"))
    )
    (net (code "70") (name "Net-(U$5-VSW)") (class "Default")
      (node (ref "U$5") (pin "8") (pinfunction "VSW_8") (pintype "output"))
      (node (ref "U$9") (pin "1") (pinfunction "P$1_1") (pintype "passive"))
    )
    (net (code "71") (name "Net-(U$6-G1)") (class "Default")
      (node (ref "R19") (pin "2") (pinfunction "2_2") (pintype "passive"))
      (node (ref "U$6") (pin "2") (pinfunction "G1_2") (pintype "passive"))
    )
    (net (code "72") (name "Net-(U$6-G2)") (class "Default")
      (node (ref "R27") (pin "1") (pinfunction "1_1") (pintype "passive"))
      (node (ref "U$6") (pin "4") (pinfunction "G2_4") (pintype "passive"))
    )
    (net (code "73") (name "Net-(U$8-G1)") (class "Default")
      (node (ref "R26") (pin "2") (pinfunction "2_2") (pintype "passive"))
      (node (ref "U$8") (pin "2") (pinfunction "G1_2") (pintype "passive"))
    )
    (net (code "74") (name "Net-(U$8-G2)") (class "Default")
      (node (ref "R28") (pin "1") (pinfunction "1_1") (pintype "passive"))
      (node (ref "U$8") (pin "4") (pinfunction "G2_4") (pintype "passive"))
    )
    (net (code "75") (name "Net-(U$12-DH)") (class "Default")
      (node (ref "U$12") (pin "8") (pinfunction "DH_8") (pintype "output"))
      (node (ref "U$20") (pin "2") (pinfunction "G_2") (pintype "passive"))
    )
    (net (code "76") (name "Net-(U$12-DL)") (class "Default")
      (node (ref "U$12") (pin "5") (pinfunction "DL_5") (pintype "output"))
      (node (ref "U$20") (pin "4") (pinfunction "G_4") (pintype "passive"))
    )
    (net (code "77") (name "Net-(U$12-SW)") (class "Default")
      (node (ref "C16") (pin "2") (pinfunction "2_2") (pintype "passive"))
      (node (ref "D1") (pin "C") (pinfunction "C_C") (pintype "passive"))
      (node (ref "U$12") (pin "7") (pinfunction "SW_7") (pintype "passive"))
    )
    (net (code "78") (name "Net-(U$15-L1)") (class "Default")
      (node (ref "C16") (pin "1") (pinfunction "1_1") (pintype "passive"))
      (node (ref "U$15") (pin "P$1") (pinfunction "L1_P$1") (pintype "passive"))
      (node (ref "U$20") (pin "1") (pinfunction "S_1") (pintype "passive"))
      (node (ref "U$20") (pin "5") (pinfunction "D_5") (pintype "passive"))
      (node (ref "U$20") (pin "6") (pinfunction "D_6") (pintype "passive"))
    )
    (net (code "79") (name "Net-(U$15-L2)") (class "Default")
      (node (ref "C19") (pin "1") (pinfunction "1_1") (pintype "passive"))
      (node (ref "C7") (pin "1") (pinfunction "1_1") (pintype "passive"))
      (node (ref "D8") (pin "C") (pinfunction "C_C") (pintype "passive"))
      (node (ref "R15") (pin "1") (pinfunction "1_1") (pintype "passive"))
      (node (ref "R9") (pin "2") (pinfunction "2_2") (pintype "passive"))
      (node (ref "U$15") (pin "P$2") (pinfunction "L2_P$2") (pintype "passive"))
      (node (ref "U$19") (pin "1") (pinfunction "S_1") (pintype "passive"))
      (node (ref "U$19") (pin "3") (pinfunction "S_3") (pintype "passive"))
    )
    (net (code "80") (name "Net-(U$16A-D+)") (class "Default")
      (node (ref "U$16") (pin "A2") (pinfunction "D-_A2") (pintype "bidirectional"))
      (node (ref "U$16") (pin "A3") (pinfunction "D+_A3") (pintype "bidirectional"))
    )
    (net (code "81") (name "Net-(U$16B-D+)") (class "Default")
      (node (ref "U$16") (pin "B2") (pinfunction "D-_B2") (pintype "bidirectional"))
      (node (ref "U$16") (pin "B3") (pinfunction "D+_B3") (pintype "bidirectional"))
    )
    (net (code "82") (name "Net-(U$19A-G)") (class "Default")
      (node (ref "R10") (pin "2") (pinfunction "2_2") (pintype "passive"))
      (node (ref "R9") (pin "1") (pinfunction "1_1") (pintype "passive"))
      (node (ref "U$19") (pin "2") (pinfunction "G_2") (pintype "passive"))
    )
    (net (code "83") (name "Net-(U$19B-G)") (class "Default")
      (node (ref "C34") (pin "1") (pinfunction "1_1") (pintype "passive"))
      (node (ref "R15") (pin "2") (pinfunction "2_2") (pintype "passive"))
      (node (ref "R22") (pin "1") (pinfunction "1_1") (pintype "passive"))
      (node (ref "U$19") (pin "4") (pinfunction "G_4") (pintype "passive"))
    )
    (net (code "84") (name "Net-(U$25-LX)") (class "Default")
      (node (ref "D2") (pin "A") (pinfunction "A_A") (pintype "passive"))
      (node (ref "U$25") (pin "1") (pinfunction "LX_1") (pintype "passive"))
      (node (ref "U$36") (pin "1") (pinfunction "P$1_1") (pintype "passive"))
    )
    (net (code "85") (name "Net-(U$27-LX)") (class "Default")
      (node (ref "D3") (pin "A") (pinfunction "A_A") (pintype "passive"))
      (node (ref "U$27") (pin "1") (pinfunction "LX_1") (pintype "passive"))
      (node (ref "U$34") (pin "1") (pinfunction "P$1_1") (pintype "passive"))
    )
    (net (code "86") (name "Net-(U$29-LX)") (class "Default")
      (node (ref "D5") (pin "A") (pinfunction "A_A") (pintype "passive"))
      (node (ref "U$29") (pin "1") (pinfunction "LX_1") (pintype "passive"))
      (node (ref "U$35") (pin "2") (pinfunction "P$2_2") (pintype "passive"))
    )
    (net (code "87") (name "Net-(U$31-LX)") (class "Default")
      (node (ref "D6") (pin "A") (pinfunction "A_A") (pintype "passive"))
      (node (ref "U$31") (pin "1") (pinfunction "LX_1") (pintype "passive"))
      (node (ref "U$33") (pin "2") (pinfunction "P$2_2") (pintype "passive"))
    )
    (net (code "88") (name "V+") (class "Default")
      (node (ref "AB") (pin "2") (pinfunction "2_2") (pintype "passive"))
      (node (ref "C13") (pin "1") (pinfunction "1_1") (pintype "passive"))
      (node (ref "C15") (pin "1") (pinfunction "1_1") (pintype "passive"))
      (node (ref "C18") (pin "1") (pinfunction "1_1") (pintype "passive"))
      (node (ref "C20") (pin "1") (pinfunction "1_1") (pintype "passive"))
      (node (ref "C21") (pin "1") (pinfunction "1_1") (pintype "passive"))
      (node (ref "C23") (pin "1") (pinfunction "1_1") (pintype "passive"))
      (node (ref "C26") (pin "1") (pinfunction "1_1") (pintype "passive"))
      (node (ref "C29") (pin "1") (pinfunction "1_1") (pintype "passive"))
      (node (ref "C32") (pin "1") (pinfunction "1_1") (pintype "passive"))
      (node (ref "C33") (pin "1") (pinfunction "1_1") (pintype "passive"))
      (node (ref "C34") (pin "2") (pinfunction "2_2") (pintype "passive"))
      (node (ref "D2") (pin "C") (pinfunction "C_C") (pintype "passive"))
      (node (ref "D3") (pin "C") (pinfunction "C_C") (pintype "passive"))
      (node (ref "D5") (pin "C") (pinfunction "C_C") (pintype "passive"))
      (node (ref "D6") (pin "C") (pinfunction "C_C") (pintype "passive"))
      (node (ref "OUT") (pin "5") (pinfunction "S_5") (pintype "passive"))
      (node (ref "OUT") (pin "6") (pinfunction "S_6") (pintype "passive"))
      (node (ref "R11") (pin "2") (pinfunction "2_2") (pintype "passive"))
      (node (ref "R23") (pin "1") (pinfunction "1_1") (pintype "passive"))
      (node (ref "R3") (pin "2") (pinfunction "2_2") (pintype "passive"))
      (node (ref "R4") (pin "2") (pinfunction "2_2") (pintype "passive"))
      (node (ref "R5") (pin "2") (pinfunction "2_2") (pintype "passive"))
      (node (ref "U$13") (pin "P$4") (pinfunction "P$4_P$4") (pintype "bidirectional"))
      (node (ref "U$13") (pin "P$5") (pinfunction "P$5_P$5") (pintype "bidirectional"))
      (node (ref "U$14") (pin "P$4") (pinfunction "P$4_P$4") (pintype "bidirectional"))
      (node (ref "U$14") (pin "P$5") (pinfunction "P$5_P$5") (pintype "bidirectional"))
      (node (ref "U$19") (pin "5") (pinfunction "D_5") (pintype "passive"))
      (node (ref "U$19") (pin "6") (pinfunction "D_6") (pintype "passive"))
      (node (ref "U$25") (pin "5") (pinfunction "VIN_5") (pintype "power_in"))
      (node (ref "U$27") (pin "5") (pinfunction "VIN_5") (pintype "power_in"))
      (node (ref "U$29") (pin "5") (pinfunction "VIN_5") (pintype "power_in"))
      (node (ref "U$31") (pin "5") (pinfunction "VIN_5") (pintype "power_in"))
      (node (ref "U$5") (pin "2") (pinfunction "VIN_2") (pintype "power_in"))
      (node (ref "U$5") (pin "6") (pinfunction "EN_6") (pintype "input"))
      (node (ref "UCAN") (pin "1") (pinfunction "1_1") (pintype "passive"))
    )
    (net (code "89") (name "unconnected-(SV2-Pad1)") (class "Default")
      (node (ref "SV2") (pin "1") (pinfunction "1_1") (pintype "passive"))
    )
    (net (code "90") (name "unconnected-(SV2-Pad2)") (class "Default")
      (node (ref "SV2") (pin "2") (pinfunction "2_2") (pintype "passive"))
    )
    (net (code "91") (name "unconnected-(SV2-Pad4)") (class "Default")
      (node (ref "SV2") (pin "4") (pinfunction "4_4") (pintype "passive"))
    )
    (net (code "92") (name "unconnected-(SV2-Pad17)") (class "Default")
      (node (ref "SV2") (pin "17") (pinfunction "17_17") (pintype "passive"))
    )
    (net (code "93") (name "unconnected-(SV2-Pad18)") (class "Default")
      (node (ref "SV2") (pin "18") (pinfunction "18_18") (pintype "passive"))
    )
    (net (code "94") (name "unconnected-(SV2-Pad22)") (class "Default")
      (node (ref "SV2") (pin "22") (pinfunction "22_22") (pintype "passive"))
    )
    (net (code "95") (name "unconnected-(U$5-PG-Pad7)") (class "Default")
      (node (ref "U$5") (pin "7") (pinfunction "PG_7") (pintype "open_collector"))
    )
    (net (code "96") (name "unconnected-(U$7-VREF-Pad5)") (class "Default")
      (node (ref "U$7") (pin "5") (pinfunction "VREF_5") (pintype "output"))
    )
  )
)
